# audiodaq_b.net
KiCad netlist of a schematic drawn in EAGLE
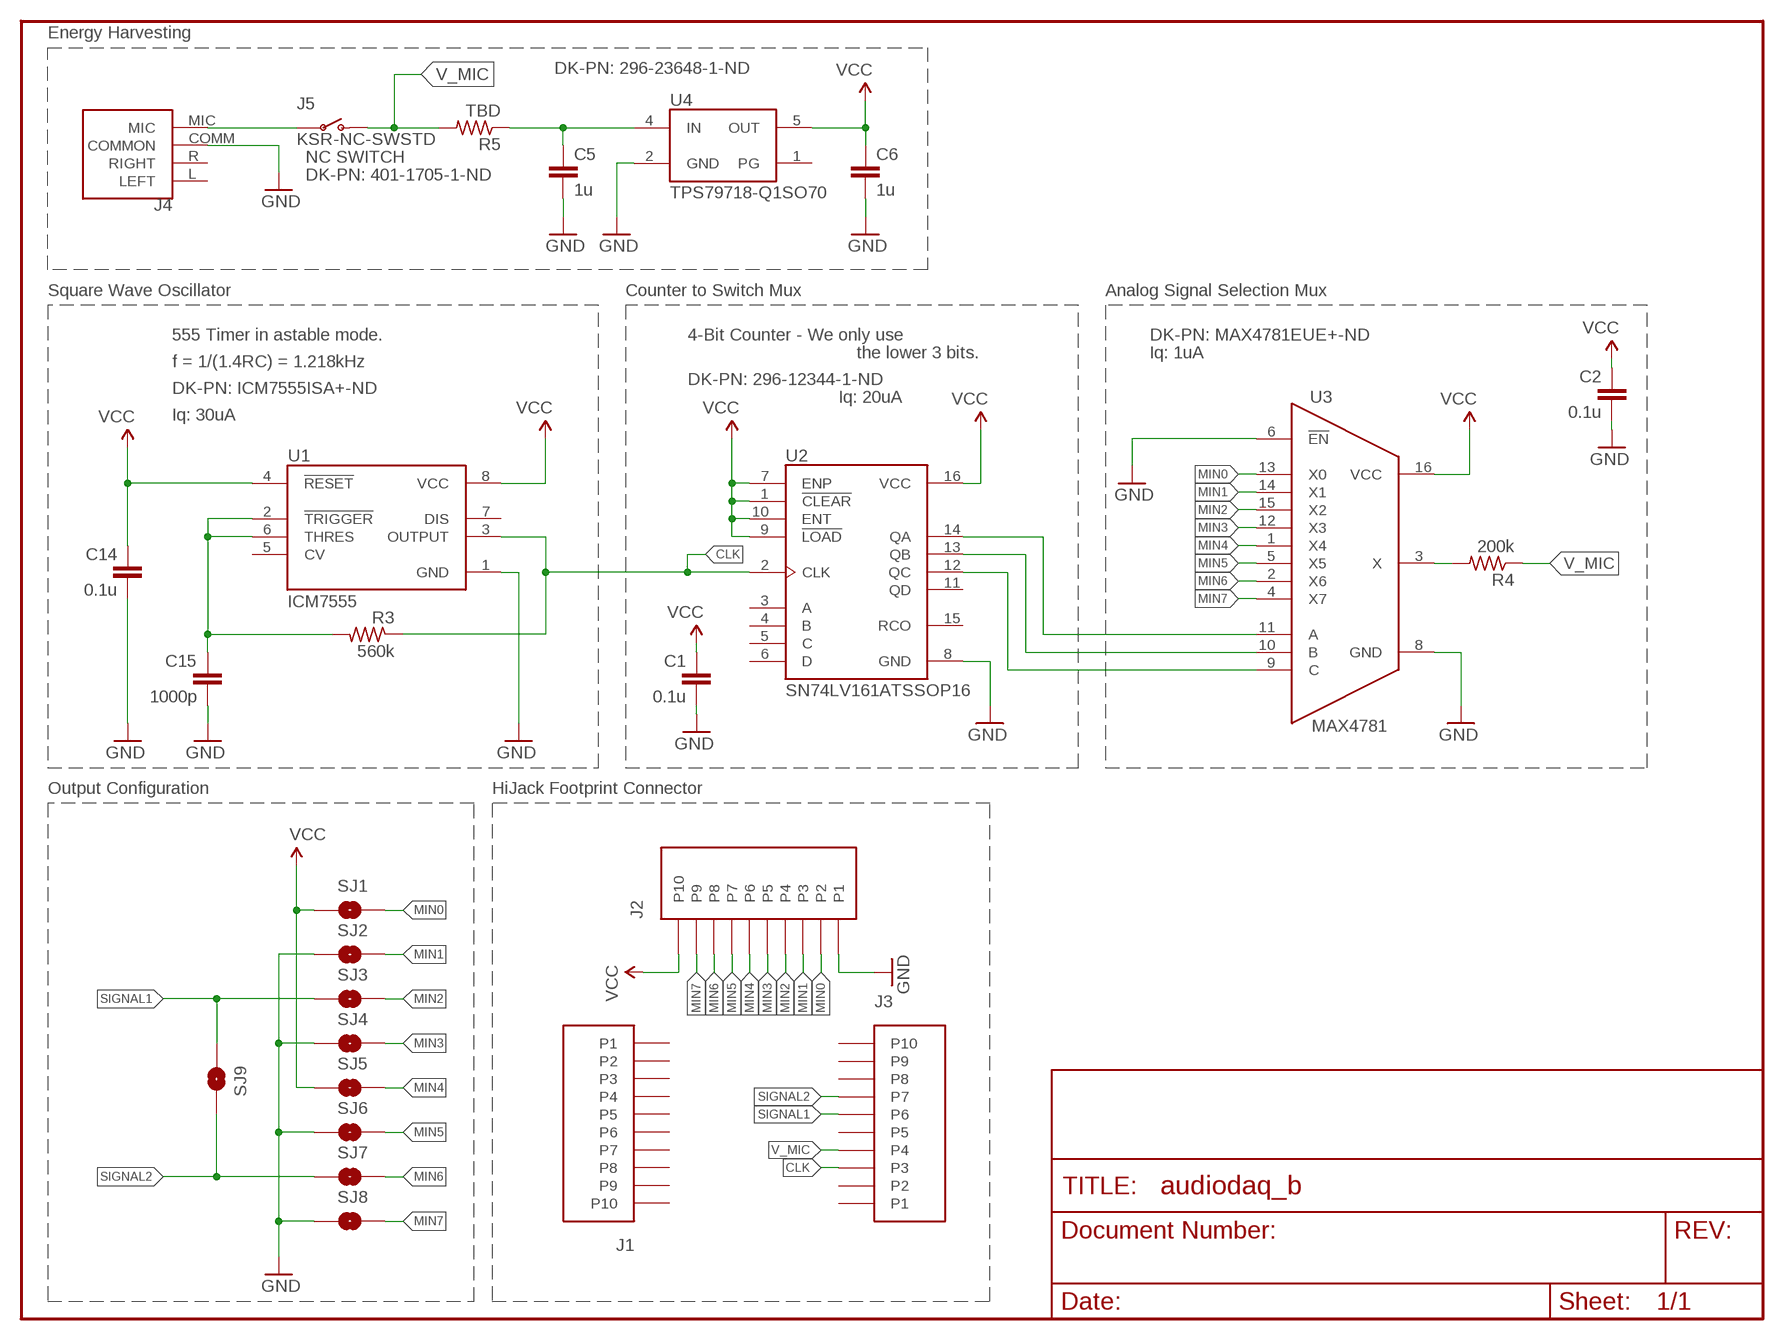
[diagram p0: schematic, sheet 1]

(export (version "E")
  (design (tool "Eeschema 10.0.6"))
  (components
    (comp (ref "C1")
      (value "0.1u")
      (footprint "eagle-import:C0603")
      (libsource (lib "eagle-import") (part "C-EUC0603"))
    )
    (comp (ref "C2")
      (value "0.1u")
      (footprint "eagle-import:C0603")
      (libsource (lib "eagle-import") (part "C-EUC0603"))
    )
    (comp (ref "C5")
      (value "1u")
      (footprint "eagle-import:C0603")
      (libsource (lib "eagle-import") (part "C-EUC0603"))
    )
    (comp (ref "C6")
      (value "1u")
      (footprint "eagle-import:C0603")
      (libsource (lib "eagle-import") (part "C-EUC0603"))
    )
    (comp (ref "C14")
      (value "0.1u")
      (footprint "eagle-import:C0603")
      (libsource (lib "eagle-import") (part "C-EUC0603"))
    )
    (comp (ref "C15")
      (value "1000p")
      (footprint "eagle-import:C0603")
      (libsource (lib "eagle-import") (part "C-EUC0603"))
    )
    (comp (ref "J1")
      (value "HEADER10POS")
      (footprint "eagle-import:10PIN2MMHEADER")
      (libsource (lib "eagle-import") (part "HEADER10POS"))
    )
    (comp (ref "J2")
      (value "HEADER10POS")
      (footprint "eagle-import:10PIN2MMHEADER")
      (libsource (lib "eagle-import") (part "HEADER10POS"))
    )
    (comp (ref "J3")
      (value "HEADER10POS")
      (footprint "eagle-import:10PIN2MMHEADER")
      (libsource (lib "eagle-import") (part "HEADER10POS"))
    )
    (comp (ref "J4")
      (value "3.5JACK4CONNSUNSTONE_QUICKTURN")
      (footprint "eagle-import:PLUGBOARDCONNECTOR_SUNSTONE")
      (libsource (lib "eagle-import") (part "3.5JACK4CONNSUNSTONE_QUICKTURN"))
    )
    (comp (ref "J5")
      (value "KSR-NC-SWSTD")
      (footprint "eagle-import:KSR_SWITCH")
      (libsource (lib "eagle-import") (part "KSR-NC-SWSTD"))
    )
    (comp (ref "R3")
      (value "560k")
      (footprint "eagle-import:R0603")
      (libsource (lib "eagle-import") (part "R-US_R0603"))
    )
    (comp (ref "R4")
      (value "200k")
      (footprint "eagle-import:R0603")
      (libsource (lib "eagle-import") (part "R-US_R0603"))
    )
    (comp (ref "R5")
      (value "TBD")
      (footprint "eagle-import:R0603")
      (libsource (lib "eagle-import") (part "R-US_R0603"))
    )
    (comp (ref "SJ1")
      (value "SOLDERJUMPERNO")
      (footprint "eagle-import:SJ_2S-NO")
      (libsource (lib "eagle-import") (part "SOLDERJUMPERNO"))
    )
    (comp (ref "SJ2")
      (value "SOLDERJUMPERNO")
      (footprint "eagle-import:SJ_2S-NO")
      (libsource (lib "eagle-import") (part "SOLDERJUMPERNO"))
    )
    (comp (ref "SJ3")
      (value "SOLDERJUMPERNO")
      (footprint "eagle-import:SJ_2S-NO")
      (libsource (lib "eagle-import") (part "SOLDERJUMPERNO"))
    )
    (comp (ref "SJ4")
      (value "SOLDERJUMPERNO")
      (footprint "eagle-import:SJ_2S-NO")
      (libsource (lib "eagle-import") (part "SOLDERJUMPERNO"))
    )
    (comp (ref "SJ5")
      (value "SOLDERJUMPERNO")
      (footprint "eagle-import:SJ_2S-NO")
      (libsource (lib "eagle-import") (part "SOLDERJUMPERNO"))
    )
    (comp (ref "SJ6")
      (value "SOLDERJUMPERNO")
      (footprint "eagle-import:SJ_2S-NO")
      (libsource (lib "eagle-import") (part "SOLDERJUMPERNO"))
    )
    (comp (ref "SJ7")
      (value "SOLDERJUMPERNO")
      (footprint "eagle-import:SJ_2S-NO")
      (libsource (lib "eagle-import") (part "SOLDERJUMPERNO"))
    )
    (comp (ref "SJ8")
      (value "SOLDERJUMPERNO")
      (footprint "eagle-import:SJ_2S-NO")
      (libsource (lib "eagle-import") (part "SOLDERJUMPERNO"))
    )
    (comp (ref "SJ9")
      (value "SOLDERJUMPERNO")
      (footprint "eagle-import:SJ_2S-NO")
      (libsource (lib "eagle-import") (part "SOLDERJUMPERNO"))
    )
    (comp (ref "U1")
      (value "ICM7555")
      (footprint "eagle-import:SOIC")
      (libsource (lib "eagle-import") (part "ICM7555"))
    )
    (comp (ref "U2")
      (value "SN74LV161ATSSOP16")
      (footprint "eagle-import:TSSOP16")
      (libsource (lib "eagle-import") (part "SN74LV161ATSSOP16"))
    )
    (comp (ref "U3")
      (value "MAX4781")
      (footprint "eagle-import:TSSOP-16")
      (libsource (lib "eagle-import") (part "MAX4781"))
    )
    (comp (ref "U4")
      (value "TPS79718-Q1SO70")
      (footprint "eagle-import:SC70")
      (libsource (lib "eagle-import") (part "TPS79718-Q1SO70"))
    )
  )
  (nets
    (net (code "1") (name "CLK") (class "Default")
      (node (ref "J3") (pin "P3") (pinfunction "P3_P3") (pintype "bidirectional"))
      (node (ref "R3") (pin "1") (pinfunction "1_1") (pintype "passive"))
      (node (ref "U1") (pin "3") (pinfunction "OUTPUT_3") (pintype "bidirectional"))
      (node (ref "U2") (pin "2") (pinfunction "CLK_2") (pintype "bidirectional"))
    )
    (net (code "2") (name "GND") (class "Default")
      (node (ref "C1") (pin "2") (pinfunction "2_2") (pintype "passive"))
      (node (ref "C14") (pin "2") (pinfunction "2_2") (pintype "passive"))
      (node (ref "C15") (pin "2") (pinfunction "2_2") (pintype "passive"))
      (node (ref "C2") (pin "2") (pinfunction "2_2") (pintype "passive"))
      (node (ref "C5") (pin "2") (pinfunction "2_2") (pintype "passive"))
      (node (ref "C6") (pin "2") (pinfunction "2_2") (pintype "passive"))
      (node (ref "J2") (pin "P1") (pinfunction "P1_P1") (pintype "bidirectional"))
      (node (ref "J4") (pin "COMM") (pinfunction "COMMON_COMM") (pintype "power_in"))
      (node (ref "SJ2") (pin "2") (pinfunction "2_2") (pintype "passive"))
      (node (ref "SJ4") (pin "2") (pinfunction "2_2") (pintype "passive"))
      (node (ref "SJ6") (pin "2") (pinfunction "2_2") (pintype "passive"))
      (node (ref "SJ8") (pin "2") (pinfunction "2_2") (pintype "passive"))
      (node (ref "U1") (pin "1") (pinfunction "GND_1") (pintype "bidirectional"))
      (node (ref "U2") (pin "8") (pinfunction "GND_8") (pintype "bidirectional"))
      (node (ref "U3") (pin "6") (pinfunction "~{EN}_6") (pintype "bidirectional"))
      (node (ref "U3") (pin "8") (pinfunction "GND_8") (pintype "bidirectional"))
      (node (ref "U4") (pin "2") (pinfunction "GND_2") (pintype "bidirectional"))
    )
    (net (code "3") (name "MIN0") (class "Default")
      (node (ref "J2") (pin "P2") (pinfunction "P2_P2") (pintype "bidirectional"))
      (node (ref "SJ1") (pin "1") (pinfunction "1_1") (pintype "passive"))
      (node (ref "U3") (pin "13") (pinfunction "X0_13") (pintype "bidirectional"))
    )
    (net (code "4") (name "MIN1") (class "Default")
      (node (ref "J2") (pin "P3") (pinfunction "P3_P3") (pintype "bidirectional"))
      (node (ref "SJ2") (pin "1") (pinfunction "1_1") (pintype "passive"))
      (node (ref "U3") (pin "14") (pinfunction "X1_14") (pintype "bidirectional"))
    )
    (net (code "5") (name "MIN2") (class "Default")
      (node (ref "J2") (pin "P4") (pinfunction "P4_P4") (pintype "bidirectional"))
      (node (ref "SJ3") (pin "1") (pinfunction "1_1") (pintype "passive"))
      (node (ref "U3") (pin "15") (pinfunction "X2_15") (pintype "bidirectional"))
    )
    (net (code "6") (name "MIN3") (class "Default")
      (node (ref "J2") (pin "P5") (pinfunction "P5_P5") (pintype "bidirectional"))
      (node (ref "SJ4") (pin "1") (pinfunction "1_1") (pintype "passive"))
      (node (ref "U3") (pin "12") (pinfunction "X3_12") (pintype "bidirectional"))
    )
    (net (code "7") (name "MIN4") (class "Default")
      (node (ref "J2") (pin "P6") (pinfunction "P6_P6") (pintype "bidirectional"))
      (node (ref "SJ5") (pin "1") (pinfunction "1_1") (pintype "passive"))
      (node (ref "U3") (pin "1") (pinfunction "X4_1") (pintype "bidirectional"))
    )
    (net (code "8") (name "MIN5") (class "Default")
      (node (ref "J2") (pin "P7") (pinfunction "P7_P7") (pintype "bidirectional"))
      (node (ref "SJ6") (pin "1") (pinfunction "1_1") (pintype "passive"))
      (node (ref "U3") (pin "5") (pinfunction "X5_5") (pintype "bidirectional"))
    )
    (net (code "9") (name "MIN6") (class "Default")
      (node (ref "J2") (pin "P8") (pinfunction "P8_P8") (pintype "bidirectional"))
      (node (ref "SJ7") (pin "1") (pinfunction "1_1") (pintype "passive"))
      (node (ref "U3") (pin "2") (pinfunction "X6_2") (pintype "bidirectional"))
    )
    (net (code "10") (name "MIN7") (class "Default")
      (node (ref "J2") (pin "P9") (pinfunction "P9_P9") (pintype "bidirectional"))
      (node (ref "SJ8") (pin "1") (pinfunction "1_1") (pintype "passive"))
      (node (ref "U3") (pin "4") (pinfunction "X7_4") (pintype "bidirectional"))
    )
    (net (code "11") (name "Net-(J5-P)") (class "Default")
      (node (ref "J4") (pin "MIC") (pinfunction "MIC_MIC") (pintype "input"))
      (node (ref "J5") (pin "P$2") (pinfunction "P_P$2") (pintype "passive"))
    )
    (net (code "12") (name "Net-(U1-THRES)") (class "Default")
      (node (ref "C15") (pin "1") (pinfunction "1_1") (pintype "passive"))
      (node (ref "R3") (pin "2") (pinfunction "2_2") (pintype "passive"))
      (node (ref "U1") (pin "2") (pinfunction "~{TRIGGER}_2") (pintype "bidirectional"))
      (node (ref "U1") (pin "6") (pinfunction "THRES_6") (pintype "bidirectional"))
    )
    (net (code "13") (name "Net-(U2-QA)") (class "Default")
      (node (ref "U2") (pin "14") (pinfunction "QA_14") (pintype "bidirectional"))
      (node (ref "U3") (pin "11") (pinfunction "A_11") (pintype "bidirectional"))
    )
    (net (code "14") (name "Net-(U2-QB)") (class "Default")
      (node (ref "U2") (pin "13") (pinfunction "QB_13") (pintype "bidirectional"))
      (node (ref "U3") (pin "10") (pinfunction "B_10") (pintype "bidirectional"))
    )
    (net (code "15") (name "Net-(U2-QC)") (class "Default")
      (node (ref "U2") (pin "12") (pinfunction "QC_12") (pintype "bidirectional"))
      (node (ref "U3") (pin "9") (pinfunction "C_9") (pintype "bidirectional"))
    )
    (net (code "16") (name "Net-(U3-X)") (class "Default")
      (node (ref "R4") (pin "2") (pinfunction "2_2") (pintype "passive"))
      (node (ref "U3") (pin "3") (pinfunction "X_3") (pintype "bidirectional"))
    )
    (net (code "17") (name "Net-(U4-IN)") (class "Default")
      (node (ref "C5") (pin "1") (pinfunction "1_1") (pintype "passive"))
      (node (ref "R5") (pin "1") (pinfunction "1_1") (pintype "passive"))
      (node (ref "U4") (pin "4") (pinfunction "IN_4") (pintype "bidirectional"))
    )
    (net (code "18") (name "SIGNAL1") (class "Default")
      (node (ref "J3") (pin "P6") (pinfunction "P6_P6") (pintype "bidirectional"))
      (node (ref "SJ3") (pin "2") (pinfunction "2_2") (pintype "passive"))
      (node (ref "SJ9") (pin "2") (pinfunction "2_2") (pintype "passive"))
    )
    (net (code "19") (name "SIGNAL2") (class "Default")
      (node (ref "J3") (pin "P7") (pinfunction "P7_P7") (pintype "bidirectional"))
      (node (ref "SJ7") (pin "2") (pinfunction "2_2") (pintype "passive"))
      (node (ref "SJ9") (pin "1") (pinfunction "1_1") (pintype "passive"))
    )
    (net (code "20") (name "VCC") (class "Default")
      (node (ref "C1") (pin "1") (pinfunction "1_1") (pintype "passive"))
      (node (ref "C14") (pin "1") (pinfunction "1_1") (pintype "passive"))
      (node (ref "C2") (pin "1") (pinfunction "1_1") (pintype "passive"))
      (node (ref "C6") (pin "1") (pinfunction "1_1") (pintype "passive"))
      (node (ref "J2") (pin "P10") (pinfunction "P10_P10") (pintype "bidirectional"))
      (node (ref "SJ1") (pin "2") (pinfunction "2_2") (pintype "passive"))
      (node (ref "SJ5") (pin "2") (pinfunction "2_2") (pintype "passive"))
      (node (ref "U1") (pin "4") (pinfunction "~{RESET}_4") (pintype "bidirectional"))
      (node (ref "U1") (pin "8") (pinfunction "VCC_8") (pintype "bidirectional"))
      (node (ref "U2") (pin "1") (pinfunction "~{CLEAR}_1") (pintype "bidirectional"))
      (node (ref "U2") (pin "10") (pinfunction "ENT_10") (pintype "bidirectional"))
      (node (ref "U2") (pin "16") (pinfunction "VCC_16") (pintype "bidirectional"))
      (node (ref "U2") (pin "7") (pinfunction "ENP_7") (pintype "bidirectional"))
      (node (ref "U2") (pin "9") (pinfunction "~{LOAD}_9") (pintype "bidirectional"))
      (node (ref "U3") (pin "16") (pinfunction "VCC_16") (pintype "bidirectional"))
      (node (ref "U4") (pin "5") (pinfunction "OUT_5") (pintype "bidirectional"))
    )
    (net (code "21") (name "V_MIC") (class "Default")
      (node (ref "J3") (pin "P4") (pinfunction "P4_P4") (pintype "bidirectional"))
      (node (ref "J5") (pin "P$1") (pinfunction "O_P$1") (pintype "passive"))
      (node (ref "R4") (pin "1") (pinfunction "1_1") (pintype "passive"))
      (node (ref "R5") (pin "2") (pinfunction "2_2") (pintype "passive"))
    )
    (net (code "22") (name "unconnected-(J1-PadP1)") (class "Default")
      (node (ref "J1") (pin "P1") (pinfunction "P1_P1") (pintype "bidirectional"))
    )
    (net (code "23") (name "unconnected-(J1-PadP2)") (class "Default")
      (node (ref "J1") (pin "P2") (pinfunction "P2_P2") (pintype "bidirectional"))
    )
    (net (code "24") (name "unconnected-(J1-PadP3)") (class "Default")
      (node (ref "J1") (pin "P3") (pinfunction "P3_P3") (pintype "bidirectional"))
    )
    (net (code "25") (name "unconnected-(J1-PadP4)") (class "Default")
      (node (ref "J1") (pin "P4") (pinfunction "P4_P4") (pintype "bidirectional"))
    )
    (net (code "26") (name "unconnected-(J1-PadP5)") (class "Default")
      (node (ref "J1") (pin "P5") (pinfunction "P5_P5") (pintype "bidirectional"))
    )
    (net (code "27") (name "unconnected-(J1-PadP6)") (class "Default")
      (node (ref "J1") (pin "P6") (pinfunction "P6_P6") (pintype "bidirectional"))
    )
    (net (code "28") (name "unconnected-(J1-PadP7)") (class "Default")
      (node (ref "J1") (pin "P7") (pinfunction "P7_P7") (pintype "bidirectional"))
    )
    (net (code "29") (name "unconnected-(J1-PadP8)") (class "Default")
      (node (ref "J1") (pin "P8") (pinfunction "P8_P8") (pintype "bidirectional"))
    )
    (net (code "30") (name "unconnected-(J1-PadP9)") (class "Default")
      (node (ref "J1") (pin "P9") (pinfunction "P9_P9") (pintype "bidirectional"))
    )
    (net (code "31") (name "unconnected-(J1-PadP10)") (class "Default")
      (node (ref "J1") (pin "P10") (pinfunction "P10_P10") (pintype "bidirectional"))
    )
    (net (code "32") (name "unconnected-(J3-PadP1)") (class "Default")
      (node (ref "J3") (pin "P1") (pinfunction "P1_P1") (pintype "bidirectional"))
    )
    (net (code "33") (name "unconnected-(J3-PadP2)") (class "Default")
      (node (ref "J3") (pin "P2") (pinfunction "P2_P2") (pintype "bidirectional"))
    )
    (net (code "34") (name "unconnected-(J3-PadP5)") (class "Default")
      (node (ref "J3") (pin "P5") (pinfunction "P5_P5") (pintype "bidirectional"))
    )
    (net (code "35") (name "unconnected-(J3-PadP8)") (class "Default")
      (node (ref "J3") (pin "P8") (pinfunction "P8_P8") (pintype "bidirectional"))
    )
    (net (code "36") (name "unconnected-(J3-PadP9)") (class "Default")
      (node (ref "J3") (pin "P9") (pinfunction "P9_P9") (pintype "bidirectional"))
    )
    (net (code "37") (name "unconnected-(J3-PadP10)") (class "Default")
      (node (ref "J3") (pin "P10") (pinfunction "P10_P10") (pintype "bidirectional"))
    )
    (net (code "38") (name "unconnected-(J4-LEFT-PadL)") (class "Default")
      (node (ref "J4") (pin "L") (pinfunction "LEFT_L") (pintype "output"))
    )
    (net (code "39") (name "unconnected-(J4-RIGHT-PadR)") (class "Default")
      (node (ref "J4") (pin "R") (pinfunction "RIGHT_R") (pintype "output"))
    )
    (net (code "40") (name "unconnected-(U1-CV-Pad5)") (class "Default")
      (node (ref "U1") (pin "5") (pinfunction "CV_5") (pintype "bidirectional"))
    )
    (net (code "41") (name "unconnected-(U1-DIS-Pad7)") (class "Default")
      (node (ref "U1") (pin "7") (pinfunction "DIS_7") (pintype "bidirectional"))
    )
    (net (code "42") (name "unconnected-(U2-A-Pad3)") (class "Default")
      (node (ref "U2") (pin "3") (pinfunction "A_3") (pintype "bidirectional"))
    )
    (net (code "43") (name "unconnected-(U2-B-Pad4)") (class "Default")
      (node (ref "U2") (pin "4") (pinfunction "B_4") (pintype "bidirectional"))
    )
    (net (code "44") (name "unconnected-(U2-C-Pad5)") (class "Default")
      (node (ref "U2") (pin "5") (pinfunction "C_5") (pintype "bidirectional"))
    )
    (net (code "45") (name "unconnected-(U2-D-Pad6)") (class "Default")
      (node (ref "U2") (pin "6") (pinfunction "D_6") (pintype "bidirectional"))
    )
    (net (code "46") (name "unconnected-(U2-QD-Pad11)") (class "Default")
      (node (ref "U2") (pin "11") (pinfunction "QD_11") (pintype "bidirectional"))
    )
    (net (code "47") (name "unconnected-(U2-RCO-Pad15)") (class "Default")
      (node (ref "U2") (pin "15") (pinfunction "RCO_15") (pintype "bidirectional"))
    )
    (net (code "48") (name "unconnected-(U4-PG-Pad1)") (class "Default")
      (node (ref "U4") (pin "1") (pinfunction "PG_1") (pintype "bidirectional"))
    )
  )
)
